# SignControlSchematic_v0.net
KiCad netlist of a schematic drawn in Altium Designer
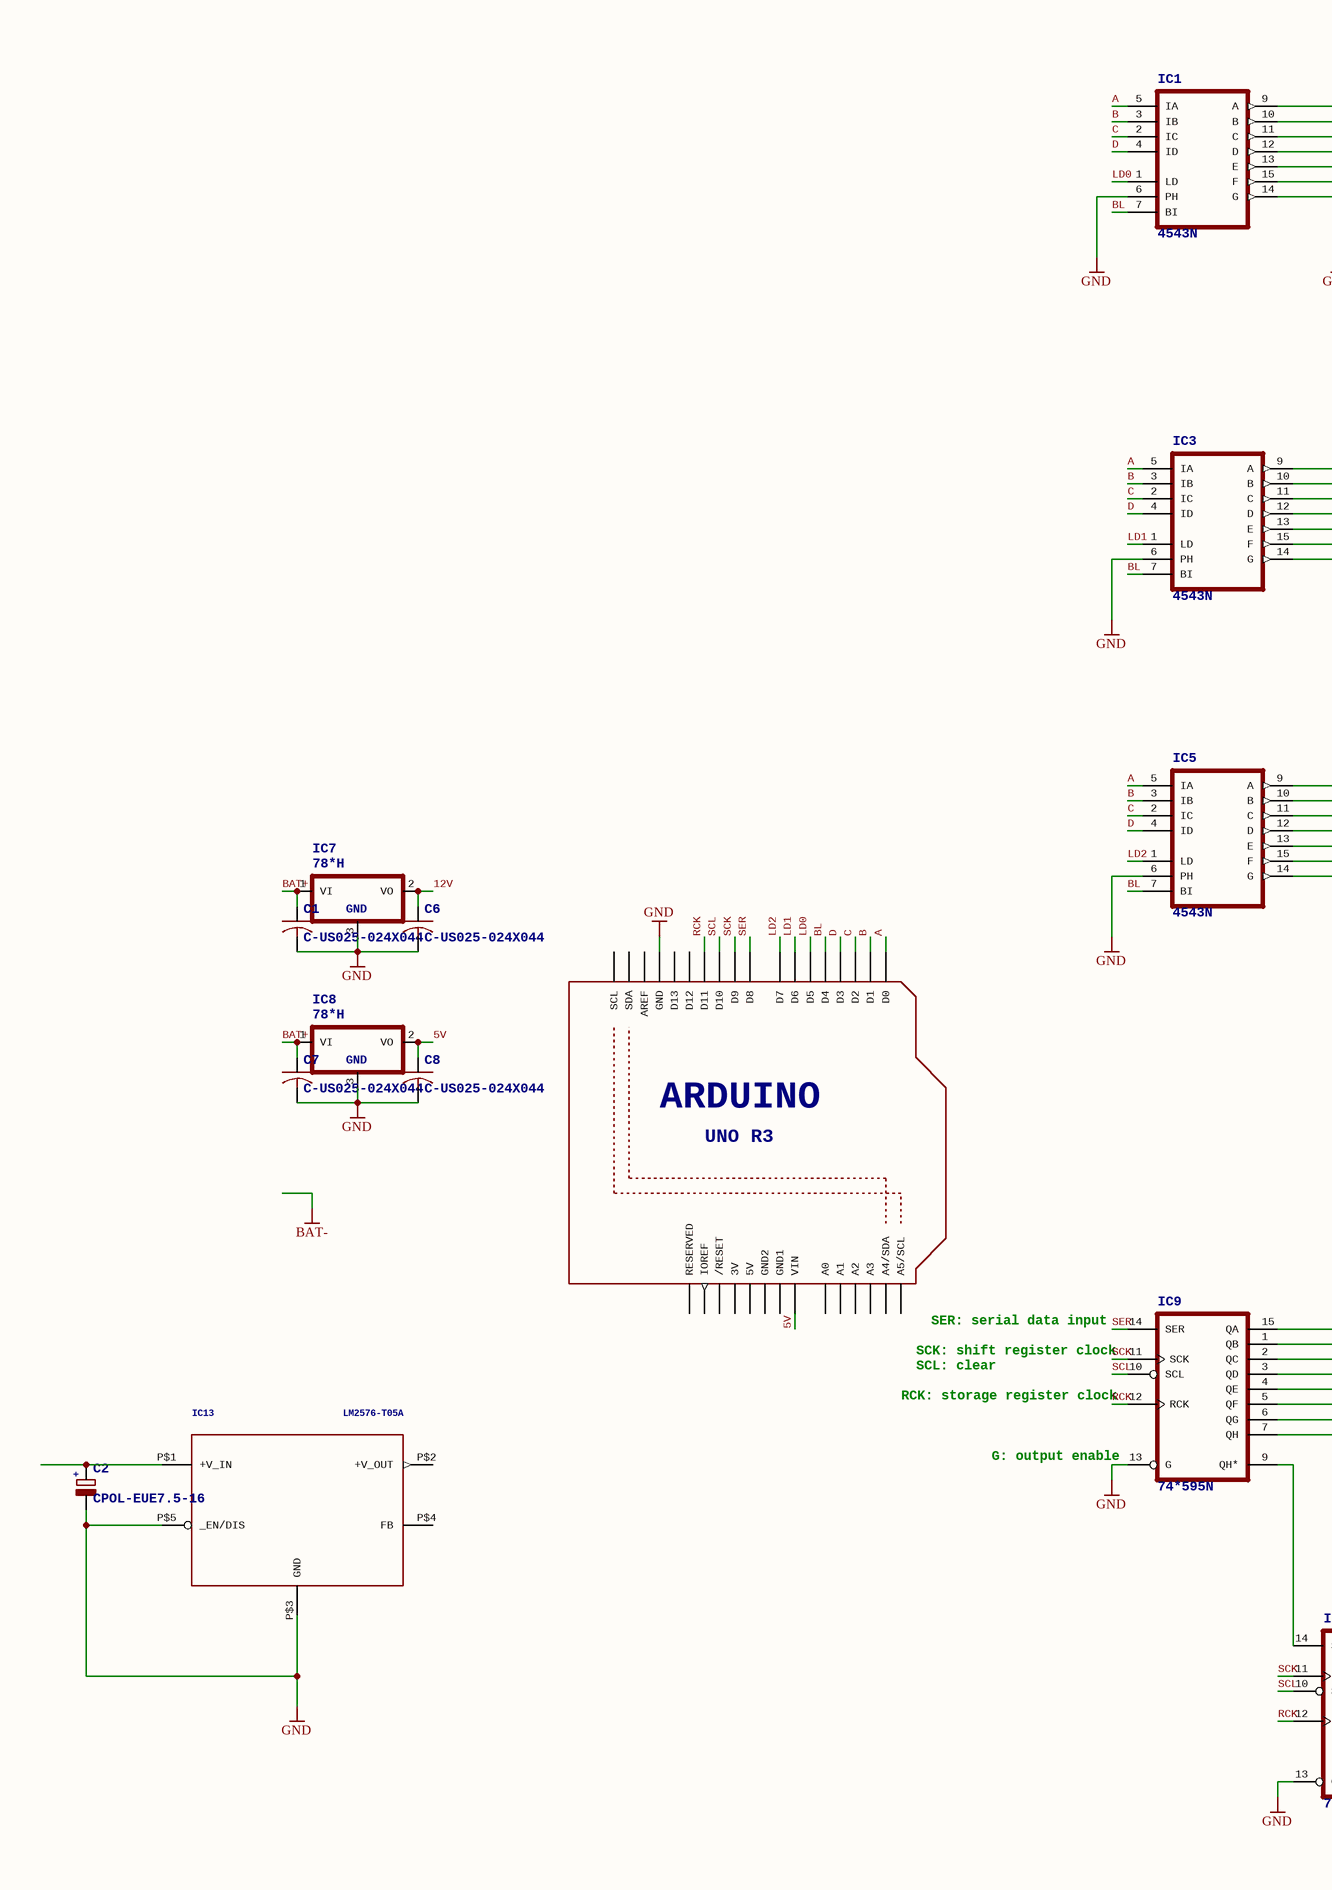
[diagram p0: SignControlSchematic_v0.SchDoc, left]
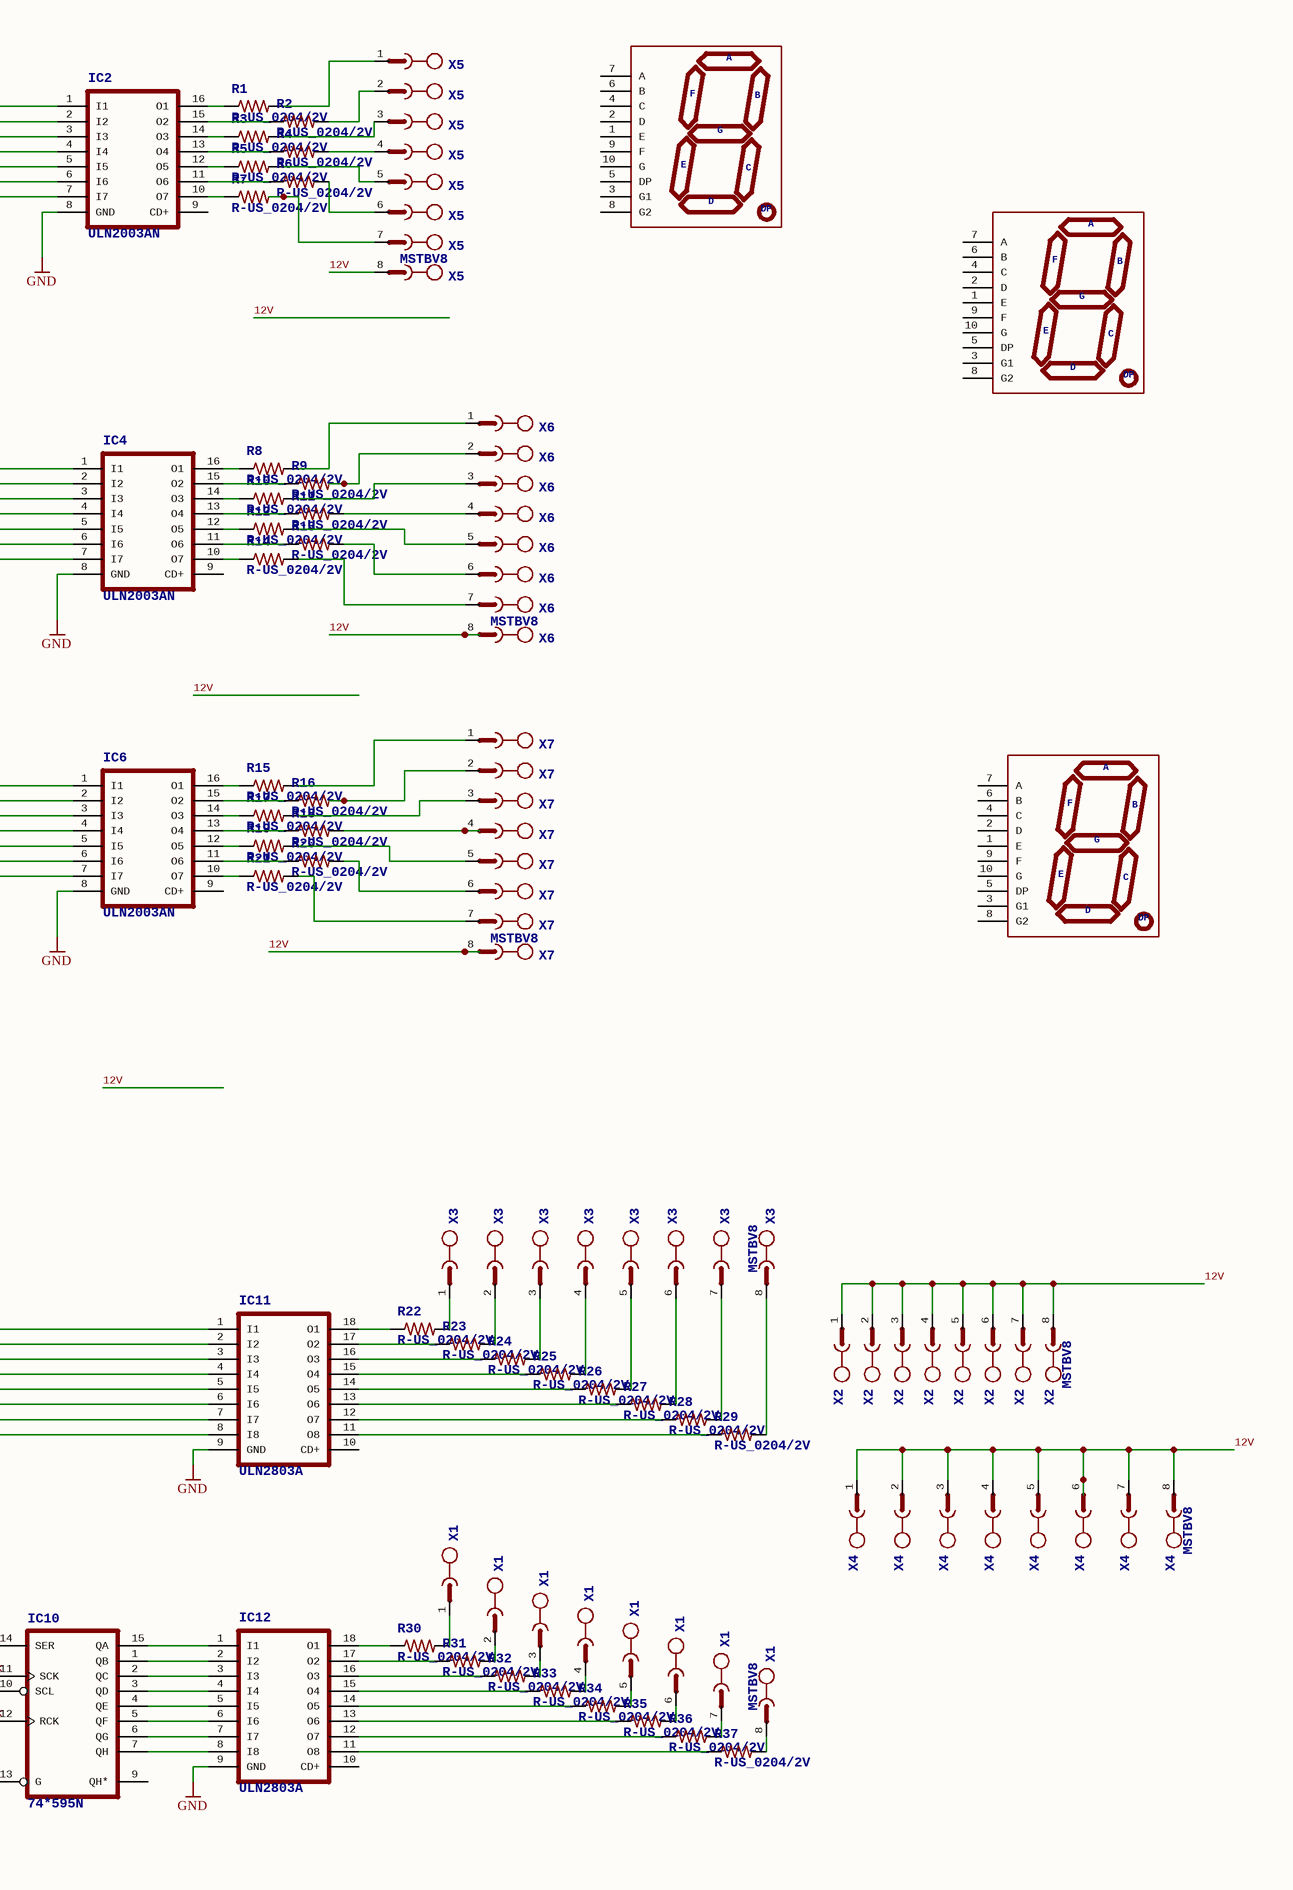
[diagram p1: SignControlSchematic_v0.SchDoc, right]

(export (version "E")
  (design (tool "Eeschema 10.0.6"))
  (components
    (comp (ref "C1")
      (value "C-US025-024X044")
      (footprint "C025-024X044")
      (description "<B>CAPACITOR</B>, American symbol")
      (fields (field (name ">NAME") "C1") (field (name ">VALUE") "C-US025-024X044"))
      (libsource (lib "adafruit") (part "C-US025-024X044"))
    )
    (comp (ref "C2")
      (value "CPOL-EUE7.5-16")
      (footprint "E7,5-16")
      (description "<B>POLARIZED CAPACITOR</B>, European symbol")
      (fields (field (name ">NAME") "C2") (field (name "+") "+") (field (name ">VALUE") "CPOL-EUE7.5-16"))
      (libsource (lib "resistor") (part "CPOL-EUE7.5-16"))
    )
    (comp (ref "C6")
      (value "C-US025-024X044")
      (footprint "C025-024X044")
      (description "<B>CAPACITOR</B>, American symbol")
      (fields (field (name ">NAME") "C6") (field (name ">VALUE") "C-US025-024X044"))
      (libsource (lib "adafruit") (part "C-US025-024X044"))
    )
    (comp (ref "C7")
      (value "C-US025-024X044")
      (footprint "C025-024X044")
      (description "<B>CAPACITOR</B>, American symbol")
      (fields (field (name ">NAME") "C7") (field (name ">VALUE") "C-US025-024X044"))
      (libsource (lib "adafruit") (part "C-US025-024X044"))
    )
    (comp (ref "C8")
      (value "C-US025-024X044")
      (footprint "C025-024X044")
      (description "<B>CAPACITOR</B>, American symbol")
      (fields (field (name ">NAME") "C8") (field (name ">VALUE") "C-US025-024X044"))
      (libsource (lib "adafruit") (part "C-US025-024X044"))
    )
    (comp (ref "IC1")
      (value "4543N")
      (footprint "DIL16")
      (description "BCD to 7-segment <b>LCD DECODER</b>")
      (fields (field (name ">NAME") "IC1") (field (name ">VALUE") "4543N"))
      (libsource (lib "45xx") (part "4543N"))
    )
    (comp (ref "IC2")
      (value "ULN2003AN")
      (footprint "DIL16")
      (description "<b>DRIVER ARRAY</b>")
      (fields (field (name ">NAME") "IC2") (field (name ">VALUE") "ULN2003AN"))
      (libsource (lib "uln-udn") (part "ULN2003AN"))
    )
    (comp (ref "IC3")
      (value "4543N")
      (footprint "DIL16")
      (description "BCD to 7-segment <b>LCD DECODER</b>")
      (fields (field (name ">NAME") "IC3") (field (name ">VALUE") "4543N"))
      (libsource (lib "45xx") (part "4543N"))
    )
    (comp (ref "IC4")
      (value "ULN2003AN")
      (footprint "DIL16")
      (description "<b>DRIVER ARRAY</b>")
      (fields (field (name ">NAME") "IC4") (field (name ">VALUE") "ULN2003AN"))
      (libsource (lib "uln-udn") (part "ULN2003AN"))
    )
    (comp (ref "IC5")
      (value "4543N")
      (footprint "DIL16")
      (description "BCD to 7-segment <b>LCD DECODER</b>")
      (fields (field (name ">NAME") "IC5") (field (name ">VALUE") "4543N"))
      (libsource (lib "45xx") (part "4543N"))
    )
    (comp (ref "IC6")
      (value "ULN2003AN")
      (footprint "DIL16")
      (description "<b>DRIVER ARRAY</b>")
      (fields (field (name ">NAME") "IC6") (field (name ">VALUE") "ULN2003AN"))
      (libsource (lib "uln-udn") (part "ULN2003AN"))
    )
    (comp (ref "IC7")
      (value "78*H")
      (footprint "TO39")
      (description "Positive <b>VOLTAGE REGULATOR</b>\n<p>\nAdded bigger pads to the TO-92 package")
      (fields (field (name ">NAME") "IC7") (field (name ">VALUE") "78*H") (field (name "GND") "GND"))
      (libsource (lib "adafruit") (part "78*H"))
    )
    (comp (ref "IC8")
      (value "78*H")
      (footprint "TO39")
      (description "Positive <b>VOLTAGE REGULATOR</b>\n<p>\nAdded bigger pads to the TO-92 package")
      (fields (field (name ">NAME") "IC8") (field (name ">VALUE") "78*H") (field (name "GND") "GND"))
      (libsource (lib "adafruit") (part "78*H"))
    )
    (comp (ref "IC9")
      (value "74*595N")
      (footprint "DIL16")
      (description "8-bit <b>SHIFT REGISTER</b>, output latch")
      (fields (field (name ">NAME") "IC9") (field (name ">VALUE") "74*595N"))
      (libsource (lib "74xx-eu") (part "74*595N"))
    )
    (comp (ref "IC10")
      (value "74*595N")
      (footprint "DIL16")
      (description "8-bit <b>SHIFT REGISTER</b>, output latch")
      (fields (field (name ">NAME") "IC10") (field (name ">VALUE") "74*595N"))
      (libsource (lib "74xx-eu") (part "74*595N"))
    )
    (comp (ref "IC11")
      (value "ULN2803A")
      (footprint "DIL18")
      (description "<b>DRIVER ARRAY</b>")
      (fields (field (name ">NAME") "IC11") (field (name ">VALUE") "ULN2803A"))
      (libsource (lib "uln-udn") (part "ULN2803A"))
    )
    (comp (ref "IC12")
      (value "ULN2803A")
      (footprint "DIL18")
      (description "<b>DRIVER ARRAY</b>")
      (fields (field (name ">NAME") "IC12") (field (name ">VALUE") "ULN2803A"))
      (libsource (lib "uln-udn") (part "ULN2803A"))
    )
    (comp (ref "IC13")
      (value "LM2576-T05A")
      (footprint "TO-220-5_IN-LINE")
      (description "LM2576/LM2576HV Series\nSIMPLE SWITCHER® 3A Step-Down Voltage Regulator\nIN-LINE PACKAGE")
      (fields (field (name ">NAME") "IC13") (field (name ">VALUE") "LM2576-T05A"))
      (libsource (lib "to220-custom") (part "LM2576-T05A"))
    )
    (comp (ref "R1")
      (value "R-US_0204/2V")
      (footprint "0204V")
      (description "<B>RESISTOR</B>, American symbol")
      (fields (field (name ">NAME") "R1") (field (name ">VALUE") "R-US_0204/2V"))
      (libsource (lib "adafruit") (part "R-US_0204/2V"))
    )
    (comp (ref "R2")
      (value "R-US_0204/2V")
      (footprint "0204V")
      (description "<B>RESISTOR</B>, American symbol")
      (fields (field (name ">NAME") "R2") (field (name ">VALUE") "R-US_0204/2V"))
      (libsource (lib "adafruit") (part "R-US_0204/2V"))
    )
    (comp (ref "R3")
      (value "R-US_0204/2V")
      (footprint "0204V")
      (description "<B>RESISTOR</B>, American symbol")
      (fields (field (name ">NAME") "R3") (field (name ">VALUE") "R-US_0204/2V"))
      (libsource (lib "adafruit") (part "R-US_0204/2V"))
    )
    (comp (ref "R4")
      (value "R-US_0204/2V")
      (footprint "0204V")
      (description "<B>RESISTOR</B>, American symbol")
      (fields (field (name ">NAME") "R4") (field (name ">VALUE") "R-US_0204/2V"))
      (libsource (lib "adafruit") (part "R-US_0204/2V"))
    )
    (comp (ref "R5")
      (value "R-US_0204/2V")
      (footprint "0204V")
      (description "<B>RESISTOR</B>, American symbol")
      (fields (field (name ">NAME") "R5") (field (name ">VALUE") "R-US_0204/2V"))
      (libsource (lib "adafruit") (part "R-US_0204/2V"))
    )
    (comp (ref "R6")
      (value "R-US_0204/2V")
      (footprint "0204V")
      (description "<B>RESISTOR</B>, American symbol")
      (fields (field (name ">NAME") "R6") (field (name ">VALUE") "R-US_0204/2V"))
      (libsource (lib "adafruit") (part "R-US_0204/2V"))
    )
    (comp (ref "R7")
      (value "R-US_0204/2V")
      (footprint "0204V")
      (description "<B>RESISTOR</B>, American symbol")
      (fields (field (name ">NAME") "R7") (field (name ">VALUE") "R-US_0204/2V"))
      (libsource (lib "adafruit") (part "R-US_0204/2V"))
    )
    (comp (ref "R8")
      (value "R-US_0204/2V")
      (footprint "0204V")
      (description "<B>RESISTOR</B>, American symbol")
      (fields (field (name ">NAME") "R8") (field (name ">VALUE") "R-US_0204/2V"))
      (libsource (lib "adafruit") (part "R-US_0204/2V"))
    )
    (comp (ref "R9")
      (value "R-US_0204/2V")
      (footprint "0204V")
      (description "<B>RESISTOR</B>, American symbol")
      (fields (field (name ">NAME") "R9") (field (name ">VALUE") "R-US_0204/2V"))
      (libsource (lib "adafruit") (part "R-US_0204/2V"))
    )
    (comp (ref "R10")
      (value "R-US_0204/2V")
      (footprint "0204V")
      (description "<B>RESISTOR</B>, American symbol")
      (fields (field (name ">NAME") "R10") (field (name ">VALUE") "R-US_0204/2V"))
      (libsource (lib "adafruit") (part "R-US_0204/2V"))
    )
    (comp (ref "R11")
      (value "R-US_0204/2V")
      (footprint "0204V")
      (description "<B>RESISTOR</B>, American symbol")
      (fields (field (name ">NAME") "R11") (field (name ">VALUE") "R-US_0204/2V"))
      (libsource (lib "adafruit") (part "R-US_0204/2V"))
    )
    (comp (ref "R12")
      (value "R-US_0204/2V")
      (footprint "0204V")
      (description "<B>RESISTOR</B>, American symbol")
      (fields (field (name ">NAME") "R12") (field (name ">VALUE") "R-US_0204/2V"))
      (libsource (lib "adafruit") (part "R-US_0204/2V"))
    )
    (comp (ref "R13")
      (value "R-US_0204/2V")
      (footprint "0204V")
      (description "<B>RESISTOR</B>, American symbol")
      (fields (field (name ">NAME") "R13") (field (name ">VALUE") "R-US_0204/2V"))
      (libsource (lib "adafruit") (part "R-US_0204/2V"))
    )
    (comp (ref "R14")
      (value "R-US_0204/2V")
      (footprint "0204V")
      (description "<B>RESISTOR</B>, American symbol")
      (fields (field (name ">NAME") "R14") (field (name ">VALUE") "R-US_0204/2V"))
      (libsource (lib "adafruit") (part "R-US_0204/2V"))
    )
    (comp (ref "R15")
      (value "R-US_0204/2V")
      (footprint "0204V")
      (description "<B>RESISTOR</B>, American symbol")
      (fields (field (name ">NAME") "R15") (field (name ">VALUE") "R-US_0204/2V"))
      (libsource (lib "adafruit") (part "R-US_0204/2V"))
    )
    (comp (ref "R16")
      (value "R-US_0204/2V")
      (footprint "0204V")
      (description "<B>RESISTOR</B>, American symbol")
      (fields (field (name ">NAME") "R16") (field (name ">VALUE") "R-US_0204/2V"))
      (libsource (lib "adafruit") (part "R-US_0204/2V"))
    )
    (comp (ref "R17")
      (value "R-US_0204/2V")
      (footprint "0204V")
      (description "<B>RESISTOR</B>, American symbol")
      (fields (field (name ">NAME") "R17") (field (name ">VALUE") "R-US_0204/2V"))
      (libsource (lib "adafruit") (part "R-US_0204/2V"))
    )
    (comp (ref "R18")
      (value "R-US_0204/2V")
      (footprint "0204V")
      (description "<B>RESISTOR</B>, American symbol")
      (fields (field (name ">NAME") "R18") (field (name ">VALUE") "R-US_0204/2V"))
      (libsource (lib "adafruit") (part "R-US_0204/2V"))
    )
    (comp (ref "R19")
      (value "R-US_0204/2V")
      (footprint "0204V")
      (description "<B>RESISTOR</B>, American symbol")
      (fields (field (name ">NAME") "R19") (field (name ">VALUE") "R-US_0204/2V"))
      (libsource (lib "adafruit") (part "R-US_0204/2V"))
    )
    (comp (ref "R20")
      (value "R-US_0204/2V")
      (footprint "0204V")
      (description "<B>RESISTOR</B>, American symbol")
      (fields (field (name ">NAME") "R20") (field (name ">VALUE") "R-US_0204/2V"))
      (libsource (lib "adafruit") (part "R-US_0204/2V"))
    )
    (comp (ref "R21")
      (value "R-US_0204/2V")
      (footprint "0204V")
      (description "<B>RESISTOR</B>, American symbol")
      (fields (field (name ">NAME") "R21") (field (name ">VALUE") "R-US_0204/2V"))
      (libsource (lib "adafruit") (part "R-US_0204/2V"))
    )
    (comp (ref "R22")
      (value "R-US_0204/2V")
      (footprint "0204V")
      (description "<B>RESISTOR</B>, American symbol")
      (fields (field (name ">NAME") "R22") (field (name ">VALUE") "R-US_0204/2V"))
      (libsource (lib "adafruit") (part "R-US_0204/2V"))
    )
    (comp (ref "R23")
      (value "R-US_0204/2V")
      (footprint "0204V")
      (description "<B>RESISTOR</B>, American symbol")
      (fields (field (name ">NAME") "R23") (field (name ">VALUE") "R-US_0204/2V"))
      (libsource (lib "adafruit") (part "R-US_0204/2V"))
    )
    (comp (ref "R24")
      (value "R-US_0204/2V")
      (footprint "0204V")
      (description "<B>RESISTOR</B>, American symbol")
      (fields (field (name ">NAME") "R24") (field (name ">VALUE") "R-US_0204/2V"))
      (libsource (lib "adafruit") (part "R-US_0204/2V"))
    )
    (comp (ref "R25")
      (value "R-US_0204/2V")
      (footprint "0204V")
      (description "<B>RESISTOR</B>, American symbol")
      (fields (field (name ">NAME") "R25") (field (name ">VALUE") "R-US_0204/2V"))
      (libsource (lib "adafruit") (part "R-US_0204/2V"))
    )
    (comp (ref "R26")
      (value "R-US_0204/2V")
      (footprint "0204V")
      (description "<B>RESISTOR</B>, American symbol")
      (fields (field (name ">NAME") "R26") (field (name ">VALUE") "R-US_0204/2V"))
      (libsource (lib "adafruit") (part "R-US_0204/2V"))
    )
    (comp (ref "R27")
      (value "R-US_0204/2V")
      (footprint "0204V")
      (description "<B>RESISTOR</B>, American symbol")
      (fields (field (name ">NAME") "R27") (field (name ">VALUE") "R-US_0204/2V"))
      (libsource (lib "adafruit") (part "R-US_0204/2V"))
    )
    (comp (ref "R28")
      (value "R-US_0204/2V")
      (footprint "0204V")
      (description "<B>RESISTOR</B>, American symbol")
      (fields (field (name ">NAME") "R28") (field (name ">VALUE") "R-US_0204/2V"))
      (libsource (lib "adafruit") (part "R-US_0204/2V"))
    )
    (comp (ref "R29")
      (value "R-US_0204/2V")
      (footprint "0204V")
      (description "<B>RESISTOR</B>, American symbol")
      (fields (field (name ">NAME") "R29") (field (name ">VALUE") "R-US_0204/2V"))
      (libsource (lib "adafruit") (part "R-US_0204/2V"))
    )
    (comp (ref "R30")
      (value "R-US_0204/2V")
      (footprint "0204V")
      (description "<B>RESISTOR</B>, American symbol")
      (fields (field (name ">NAME") "R30") (field (name ">VALUE") "R-US_0204/2V"))
      (libsource (lib "adafruit") (part "R-US_0204/2V"))
    )
    (comp (ref "R31")
      (value "R-US_0204/2V")
      (footprint "0204V")
      (description "<B>RESISTOR</B>, American symbol")
      (fields (field (name ">NAME") "R31") (field (name ">VALUE") "R-US_0204/2V"))
      (libsource (lib "adafruit") (part "R-US_0204/2V"))
    )
    (comp (ref "R32")
      (value "R-US_0204/2V")
      (footprint "0204V")
      (description "<B>RESISTOR</B>, American symbol")
      (fields (field (name ">NAME") "R32") (field (name ">VALUE") "R-US_0204/2V"))
      (libsource (lib "adafruit") (part "R-US_0204/2V"))
    )
    (comp (ref "R33")
      (value "R-US_0204/2V")
      (footprint "0204V")
      (description "<B>RESISTOR</B>, American symbol")
      (fields (field (name ">NAME") "R33") (field (name ">VALUE") "R-US_0204/2V"))
      (libsource (lib "adafruit") (part "R-US_0204/2V"))
    )
    (comp (ref "R34")
      (value "R-US_0204/2V")
      (footprint "0204V")
      (description "<B>RESISTOR</B>, American symbol")
      (fields (field (name ">NAME") "R34") (field (name ">VALUE") "R-US_0204/2V"))
      (libsource (lib "adafruit") (part "R-US_0204/2V"))
    )
    (comp (ref "R35")
      (value "R-US_0204/2V")
      (footprint "0204V")
      (description "<B>RESISTOR</B>, American symbol")
      (fields (field (name ">NAME") "R35") (field (name ">VALUE") "R-US_0204/2V"))
      (libsource (lib "adafruit") (part "R-US_0204/2V"))
    )
    (comp (ref "R36")
      (value "R-US_0204/2V")
      (footprint "0204V")
      (description "<B>RESISTOR</B>, American symbol")
      (fields (field (name ">NAME") "R36") (field (name ">VALUE") "R-US_0204/2V"))
      (libsource (lib "adafruit") (part "R-US_0204/2V"))
    )
    (comp (ref "R37")
      (value "R-US_0204/2V")
      (footprint "0204V")
      (description "<B>RESISTOR</B>, American symbol")
      (fields (field (name ">NAME") "R37") (field (name ">VALUE") "R-US_0204/2V"))
      (libsource (lib "adafruit") (part "R-US_0204/2V"))
    )
    (comp (ref "U$1")
      (value "7-SEGMENT-DISPLAY-1\"-RED")
      (footprint "7-SEGMENT-1\"PTH")
      (fields
        (field (name "A") "A")
        (field (name "B") "B")
        (field (name "C") "C")
        (field (name "D") "D")
        (field (name "E") "E")
        (field (name "F") "F")
        (field (name "G") "G")
        (field (name "DP") "DP")
      )
      (libsource (lib "SparkFun-Displays") (part "7-SEGMENT-DISPLAY-1{dblquote}-RED"))
    )
    (comp (ref "U$2")
      (value "7-SEGMENT-DISPLAY-1\"-RED")
      (footprint "7-SEGMENT-1\"PTH")
      (fields
        (field (name "A") "A")
        (field (name "B") "B")
        (field (name "C") "C")
        (field (name "D") "D")
        (field (name "E") "E")
        (field (name "F") "F")
        (field (name "G") "G")
        (field (name "DP") "DP")
      )
      (libsource (lib "SparkFun-Displays") (part "7-SEGMENT-DISPLAY-1{dblquote}-RED"))
    )
    (comp (ref "U$3")
      (value "7-SEGMENT-DISPLAY-1\"-RED")
      (footprint "7-SEGMENT-1\"PTH")
      (fields
        (field (name "A") "A")
        (field (name "B") "B")
        (field (name "C") "C")
        (field (name "D") "D")
        (field (name "E") "E")
        (field (name "F") "F")
        (field (name "G") "G")
        (field (name "DP") "DP")
      )
      (libsource (lib "SparkFun-Displays") (part "7-SEGMENT-DISPLAY-1{dblquote}-RED"))
    )
    (comp (ref "U1")
      (value "ARDUINOR3-BPLACE")
      (footprint "ARDUINOR3-BPLACE")
      (fields (field (name "ARDUINO") "ARDUINO") (field (name "UNO R3") "UNO R3"))
      (libsource (lib "adafruit") (part "ARDUINOR3-BPLACE"))
    )
    (comp (ref "X1")
      (value "MSTBV8")
      (footprint "MSTBV8")
      (description "<b>PHOENIX</b>")
      (fields
        (field (name "MPN") "MSTBV 2,5/8-GF-5.08")
        (field (name ">NAME") "X1")
        (field (name ">VALUE") "MSTBV8")
      )
      (libsource (lib "") (part "MSTBV8_4"))
    )
    (comp (ref "X2")
      (value "MSTBV8")
      (footprint "MSTBV8")
      (description "<b>PHOENIX</b>")
      (fields
        (field (name "MPN") "MSTBV 2,5/8-GF-5.08")
        (field (name ">NAME") "X2")
        (field (name ">VALUE") "MSTBV8")
      )
      (libsource (lib "") (part "MSTBV8_4"))
    )
    (comp (ref "X3")
      (value "MSTBV8")
      (footprint "MSTBV8")
      (description "<b>PHOENIX</b>")
      (fields
        (field (name "MPN") "MSTBV 2,5/8-GF-5.08")
        (field (name ">NAME") "X3")
        (field (name ">VALUE") "MSTBV8")
      )
      (libsource (lib "") (part "MSTBV8_1"))
    )
    (comp (ref "X4")
      (value "MSTBV8")
      (footprint "MSTBV8")
      (description "<b>PHOENIX</b>")
      (fields
        (field (name "MPN") "MSTBV 2,5/8-GF-5.08")
        (field (name ">NAME") "X4")
        (field (name ">VALUE") "MSTBV8")
      )
      (libsource (lib "") (part "MSTBV8_7"))
    )
    (comp (ref "X5")
      (value "MSTBV8")
      (footprint "MSTBV8")
      (description "<b>PHOENIX</b>")
      (fields
        (field (name "MPN") "MSTBV 2,5/8-GF-5.08")
        (field (name ">VALUE") "MSTBV8")
        (field (name ">NAME") "X5")
      )
      (libsource (lib "") (part "MSTBV8_7"))
    )
    (comp (ref "X6")
      (value "MSTBV8")
      (footprint "MSTBV8")
      (description "<b>PHOENIX</b>")
      (fields
        (field (name "MPN") "MSTBV 2,5/8-GF-5.08")
        (field (name ">VALUE") "MSTBV8")
        (field (name ">NAME") "X6")
      )
      (libsource (lib "con-phoenix-508") (part "MSTBV8"))
    )
    (comp (ref "X7")
      (value "MSTBV8")
      (footprint "MSTBV8")
      (description "<b>PHOENIX</b>")
      (fields
        (field (name "MPN") "MSTBV 2,5/8-GF-5.08")
        (field (name ">NAME") "X7")
        (field (name ">VALUE") "MSTBV8")
      )
      (libsource (lib "") (part "MSTBV8_4"))
    )
  )
  (nets
    (net (code "1") (name "/5V") (class "Default")
      (node (ref "C8") (pin "1") (pinfunction "1_1") (pintype "passive"))
      (node (ref "IC8") (pin "2") (pinfunction "VO_2") (pintype "passive"))
      (node (ref "U1") (pin "VIN") (pinfunction "VIN_VIN") (pintype "power_in"))
    )
    (net (code "2") (name "/12V") (class "Default")
      (node (ref "C6") (pin "1") (pinfunction "1_1") (pintype "passive"))
      (node (ref "IC7") (pin "2") (pinfunction "VO_2") (pintype "passive"))
      (node (ref "X2") (pin "1") (pinfunction "1_1") (pintype "passive"))
      (node (ref "X2") (pin "2") (pinfunction "1_2") (pintype "passive"))
      (node (ref "X2") (pin "3") (pinfunction "1_3") (pintype "passive"))
      (node (ref "X2") (pin "4") (pinfunction "1_4") (pintype "passive"))
      (node (ref "X2") (pin "5") (pinfunction "1_5") (pintype "passive"))
      (node (ref "X2") (pin "6") (pinfunction "1_6") (pintype "passive"))
      (node (ref "X2") (pin "7") (pinfunction "1_7") (pintype "passive"))
      (node (ref "X2") (pin "8") (pinfunction "1_8") (pintype "passive"))
      (node (ref "X4") (pin "1") (pinfunction "1_1") (pintype "passive"))
      (node (ref "X4") (pin "2") (pinfunction "1_2") (pintype "passive"))
      (node (ref "X4") (pin "3") (pinfunction "1_3") (pintype "passive"))
      (node (ref "X4") (pin "4") (pinfunction "1_4") (pintype "passive"))
      (node (ref "X4") (pin "5") (pinfunction "1_5") (pintype "passive"))
      (node (ref "X4") (pin "6") (pinfunction "1_6") (pintype "passive"))
      (node (ref "X4") (pin "7") (pinfunction "1_7") (pintype "passive"))
      (node (ref "X4") (pin "8") (pinfunction "1_8") (pintype "passive"))
      (node (ref "X5") (pin "8") (pinfunction "1_8") (pintype "passive"))
      (node (ref "X6") (pin "8") (pinfunction "1_8") (pintype "passive"))
      (node (ref "X7") (pin "8") (pinfunction "1_8") (pintype "passive"))
    )
    (net (code "3") (name "/A") (class "Default")
      (node (ref "IC1") (pin "5") (pinfunction "IA_5") (pintype "passive"))
      (node (ref "IC3") (pin "5") (pinfunction "IA_5") (pintype "passive"))
      (node (ref "IC5") (pin "5") (pinfunction "IA_5") (pintype "passive"))
      (node (ref "U1") (pin "D0") (pinfunction "D0_D0") (pintype "passive"))
    )
    (net (code "4") (name "/B") (class "Default")
      (node (ref "IC1") (pin "3") (pinfunction "IB_3") (pintype "passive"))
      (node (ref "IC3") (pin "3") (pinfunction "IB_3") (pintype "passive"))
      (node (ref "IC5") (pin "3") (pinfunction "IB_3") (pintype "passive"))
      (node (ref "U1") (pin "D1") (pinfunction "D1_D1") (pintype "passive"))
    )
    (net (code "5") (name "/BAT+") (class "Default")
      (node (ref "C1") (pin "1") (pinfunction "1_1") (pintype "passive"))
      (node (ref "C7") (pin "1") (pinfunction "1_1") (pintype "passive"))
      (node (ref "IC7") (pin "1") (pinfunction "VI_1") (pintype "passive"))
      (node (ref "IC8") (pin "1") (pinfunction "VI_1") (pintype "passive"))
    )
    (net (code "6") (name "/BL") (class "Default")
      (node (ref "IC1") (pin "7") (pinfunction "BI_7") (pintype "passive"))
      (node (ref "IC3") (pin "7") (pinfunction "BI_7") (pintype "passive"))
      (node (ref "IC5") (pin "7") (pinfunction "BI_7") (pintype "passive"))
      (node (ref "U1") (pin "D4") (pinfunction "D4_D4") (pintype "passive"))
    )
    (net (code "7") (name "/C") (class "Default")
      (node (ref "IC1") (pin "2") (pinfunction "IC_2") (pintype "passive"))
      (node (ref "IC3") (pin "2") (pinfunction "IC_2") (pintype "passive"))
      (node (ref "IC5") (pin "2") (pinfunction "IC_2") (pintype "passive"))
      (node (ref "U1") (pin "D2") (pinfunction "D2_D2") (pintype "passive"))
    )
    (net (code "8") (name "/D") (class "Default")
      (node (ref "IC1") (pin "4") (pinfunction "ID_4") (pintype "passive"))
      (node (ref "IC3") (pin "4") (pinfunction "ID_4") (pintype "passive"))
      (node (ref "IC5") (pin "4") (pinfunction "ID_4") (pintype "passive"))
      (node (ref "U1") (pin "D3") (pinfunction "D3_D3") (pintype "passive"))
    )
    (net (code "9") (name "/LD0") (class "Default")
      (node (ref "IC1") (pin "1") (pinfunction "LD_1") (pintype "passive"))
      (node (ref "U1") (pin "D5") (pinfunction "D5_D5") (pintype "passive"))
    )
    (net (code "10") (name "/LD1") (class "Default")
      (node (ref "IC3") (pin "1") (pinfunction "LD_1") (pintype "passive"))
      (node (ref "U1") (pin "D6") (pinfunction "D6_D6") (pintype "passive"))
    )
    (net (code "11") (name "/LD2") (class "Default")
      (node (ref "IC5") (pin "1") (pinfunction "LD_1") (pintype "passive"))
      (node (ref "U1") (pin "D7") (pinfunction "D7_D7") (pintype "passive"))
    )
    (net (code "12") (name "/RCK") (class "Default")
      (node (ref "IC10") (pin "12") (pinfunction "RCK_12") (pintype "passive"))
      (node (ref "IC9") (pin "12") (pinfunction "RCK_12") (pintype "passive"))
      (node (ref "U1") (pin "D11") (pinfunction "D11_D11") (pintype "passive"))
    )
    (net (code "13") (name "/SCK") (class "Default")
      (node (ref "IC10") (pin "11") (pinfunction "SCK_11") (pintype "passive"))
      (node (ref "IC9") (pin "11") (pinfunction "SCK_11") (pintype "passive"))
      (node (ref "U1") (pin "D9") (pinfunction "D9_D9") (pintype "passive"))
    )
    (net (code "14") (name "/SCL") (class "Default")
      (node (ref "IC10") (pin "10") (pinfunction "SCL_10") (pintype "passive"))
      (node (ref "IC9") (pin "10") (pinfunction "SCL_10") (pintype "passive"))
      (node (ref "U1") (pin "D10") (pinfunction "D10_D10") (pintype "passive"))
    )
    (net (code "15") (name "/SER") (class "Default")
      (node (ref "IC9") (pin "14") (pinfunction "SER_14") (pintype "passive"))
      (node (ref "U1") (pin "D8") (pinfunction "D8_D8") (pintype "passive"))
    )
    (net (code "17") (name "GND") (class "Default")
      (node (ref "C1") (pin "2") (pinfunction "2_2") (pintype "passive"))
      (node (ref "C2") (pin "-") (pinfunction "-_-") (pintype "passive"))
      (node (ref "C6") (pin "2") (pinfunction "2_2") (pintype "passive"))
      (node (ref "C7") (pin "2") (pinfunction "2_2") (pintype "passive"))
      (node (ref "C8") (pin "2") (pinfunction "2_2") (pintype "passive"))
      (node (ref "IC1") (pin "6") (pinfunction "PH_6") (pintype "passive"))
      (node (ref "IC10") (pin "13") (pinfunction "G_13") (pintype "passive"))
      (node (ref "IC11") (pin "9") (pinfunction "GND_9") (pintype "power_in"))
      (node (ref "IC12") (pin "9") (pinfunction "GND_9") (pintype "power_in"))
      (node (ref "IC13") (pin "P$3") (pinfunction "GND_P$3") (pintype "power_in"))
      (node (ref "IC13") (pin "P$5") (pinfunction "_EN/DIS_P$5") (pintype "passive"))
      (node (ref "IC2") (pin "8") (pinfunction "GND_8") (pintype "power_in"))
      (node (ref "IC3") (pin "6") (pinfunction "PH_6") (pintype "passive"))
      (node (ref "IC4") (pin "8") (pinfunction "GND_8") (pintype "power_in"))
      (node (ref "IC5") (pin "6") (pinfunction "PH_6") (pintype "passive"))
      (node (ref "IC6") (pin "8") (pinfunction "GND_8") (pintype "power_in"))
      (node (ref "IC7") (pin "3") (pinfunction "GND_3") (pintype "passive"))
      (node (ref "IC8") (pin "3") (pinfunction "GND_3") (pintype "passive"))
      (node (ref "IC9") (pin "13") (pinfunction "G_13") (pintype "passive"))
      (node (ref "U1") (pin "GND") (pinfunction "GND_GND") (pintype "power_in"))
    )
    (net (code "18") (name "Net-(IC1-A)") (class "Default")
      (node (ref "IC1") (pin "9") (pinfunction "A_9") (pintype "output"))
      (node (ref "IC2") (pin "1") (pinfunction "I1_1") (pintype "passive"))
    )
    (net (code "19") (name "Net-(IC1-B)") (class "Default")
      (node (ref "IC1") (pin "10") (pinfunction "B_10") (pintype "output"))
      (node (ref "IC2") (pin "2") (pinfunction "I2_2") (pintype "passive"))
    )
    (net (code "20") (name "Net-(IC1-C)") (class "Default")
      (node (ref "IC1") (pin "11") (pinfunction "C_11") (pintype "output"))
      (node (ref "IC2") (pin "3") (pinfunction "I3_3") (pintype "passive"))
    )
    (net (code "21") (name "Net-(IC1-D)") (class "Default")
      (node (ref "IC1") (pin "12") (pinfunction "D_12") (pintype "output"))
      (node (ref "IC2") (pin "4") (pinfunction "I4_4") (pintype "passive"))
    )
    (net (code "22") (name "Net-(IC1-E)") (class "Default")
      (node (ref "IC1") (pin "13") (pinfunction "E_13") (pintype "output"))
      (node (ref "IC2") (pin "5") (pinfunction "I5_5") (pintype "passive"))
    )
    (net (code "23") (name "Net-(IC1-F)") (class "Default")
      (node (ref "IC1") (pin "15") (pinfunction "F_15") (pintype "output"))
      (node (ref "IC2") (pin "6") (pinfunction "I6_6") (pintype "passive"))
    )
    (net (code "24") (name "Net-(IC1-G)") (class "Default")
      (node (ref "IC1") (pin "14") (pinfunction "G_14") (pintype "output"))
      (node (ref "IC2") (pin "7") (pinfunction "I7_7") (pintype "passive"))
    )
    (net (code "25") (name "Net-(IC2-O1)") (class "Default")
      (node (ref "IC2") (pin "16") (pinfunction "O1_16") (pintype "open_collector"))
      (node (ref "R1") (pin "1") (pinfunction "1_1") (pintype "passive"))
    )
    (net (code "26") (name "Net-(IC2-O2)") (class "Default")
      (node (ref "IC2") (pin "15") (pinfunction "O2_15") (pintype "open_collector"))
      (node (ref "R2") (pin "1") (pinfunction "1_1") (pintype "passive"))
    )
    (net (code "27") (name "Net-(IC2-O3)") (class "Default")
      (node (ref "IC2") (pin "14") (pinfunction "O3_14") (pintype "open_collector"))
      (node (ref "R3") (pin "1") (pinfunction "1_1") (pintype "passive"))
    )
    (net (code "28") (name "Net-(IC2-O4)") (class "Default")
      (node (ref "IC2") (pin "13") (pinfunction "O4_13") (pintype "open_collector"))
      (node (ref "R4") (pin "1") (pinfunction "1_1") (pintype "passive"))
    )
    (net (code "29") (name "Net-(IC2-O5)") (class "Default")
      (node (ref "IC2") (pin "12") (pinfunction "O5_12") (pintype "open_collector"))
      (node (ref "R5") (pin "1") (pinfunction "1_1") (pintype "passive"))
    )
    (net (code "30") (name "Net-(IC2-O6)") (class "Default")
      (node (ref "IC2") (pin "11") (pinfunction "O6_11") (pintype "open_collector"))
      (node (ref "R6") (pin "1") (pinfunction "1_1") (pintype "passive"))
    )
    (net (code "31") (name "Net-(IC2-O7)") (class "Default")
      (node (ref "IC2") (pin "10") (pinfunction "O7_10") (pintype "open_collector"))
      (node (ref "R7") (pin "1") (pinfunction "1_1") (pintype "passive"))
    )
    (net (code "32") (name "Net-(IC3-A)") (class "Default")
      (node (ref "IC3") (pin "9") (pinfunction "A_9") (pintype "output"))
      (node (ref "IC4") (pin "1") (pinfunction "I1_1") (pintype "passive"))
    )
    (net (code "33") (name "Net-(IC3-B)") (class "Default")
      (node (ref "IC3") (pin "10") (pinfunction "B_10") (pintype "output"))
      (node (ref "IC4") (pin "2") (pinfunction "I2_2") (pintype "passive"))
    )
    (net (code "34") (name "Net-(IC3-C)") (class "Default")
      (node (ref "IC3") (pin "11") (pinfunction "C_11") (pintype "output"))
      (node (ref "IC4") (pin "3") (pinfunction "I3_3") (pintype "passive"))
    )
    (net (code "35") (name "Net-(IC3-D)") (class "Default")
      (node (ref "IC3") (pin "12") (pinfunction "D_12") (pintype "output"))
      (node (ref "IC4") (pin "4") (pinfunction "I4_4") (pintype "passive"))
    )
    (net (code "36") (name "Net-(IC3-E)") (class "Default")
      (node (ref "IC3") (pin "13") (pinfunction "E_13") (pintype "output"))
      (node (ref "IC4") (pin "5") (pinfunction "I5_5") (pintype "passive"))
    )
    (net (code "37") (name "Net-(IC3-F)") (class "Default")
      (node (ref "IC3") (pin "15") (pinfunction "F_15") (pintype "output"))
      (node (ref "IC4") (pin "6") (pinfunction "I6_6") (pintype "passive"))
    )
    (net (code "38") (name "Net-(IC3-G)") (class "Default")
      (node (ref "IC3") (pin "14") (pinfunction "G_14") (pintype "output"))
      (node (ref "IC4") (pin "7") (pinfunction "I7_7") (pintype "passive"))
    )
    (net (code "39") (name "Net-(IC4-O1)") (class "Default")
      (node (ref "IC4") (pin "16") (pinfunction "O1_16") (pintype "open_collector"))
      (node (ref "R8") (pin "1") (pinfunction "1_1") (pintype "passive"))
    )
    (net (code "40") (name "Net-(IC4-O2)") (class "Default")
      (node (ref "IC4") (pin "15") (pinfunction "O2_15") (pintype "open_collector"))
      (node (ref "R9") (pin "1") (pinfunction "1_1") (pintype "passive"))
    )
    (net (code "41") (name "Net-(IC4-O3)") (class "Default")
      (node (ref "IC4") (pin "14") (pinfunction "O3_14") (pintype "open_collector"))
      (node (ref "R10") (pin "1") (pinfunction "1_1") (pintype "passive"))
    )
    (net (code "42") (name "Net-(IC4-O4)") (class "Default")
      (node (ref "IC4") (pin "13") (pinfunction "O4_13") (pintype "open_collector"))
      (node (ref "R11") (pin "1") (pinfunction "1_1") (pintype "passive"))
    )
    (net (code "43") (name "Net-(IC4-O5)") (class "Default")
      (node (ref "IC4") (pin "12") (pinfunction "O5_12") (pintype "open_collector"))
      (node (ref "R12") (pin "1") (pinfunction "1_1") (pintype "passive"))
    )
    (net (code "44") (name "Net-(IC4-O6)") (class "Default")
      (node (ref "IC4") (pin "11") (pinfunction "O6_11") (pintype "open_collector"))
      (node (ref "R13") (pin "1") (pinfunction "1_1") (pintype "passive"))
    )
    (net (code "45") (name "Net-(IC4-O7)") (class "Default")
      (node (ref "IC4") (pin "10") (pinfunction "O7_10") (pintype "open_collector"))
      (node (ref "R14") (pin "1") (pinfunction "1_1") (pintype "passive"))
    )
    (net (code "46") (name "Net-(IC5-A)") (class "Default")
      (node (ref "IC5") (pin "9") (pinfunction "A_9") (pintype "output"))
      (node (ref "IC6") (pin "1") (pinfunction "I1_1") (pintype "passive"))
    )
    (net (code "47") (name "Net-(IC5-B)") (class "Default")
      (node (ref "IC5") (pin "10") (pinfunction "B_10") (pintype "output"))
      (node (ref "IC6") (pin "2") (pinfunction "I2_2") (pintype "passive"))
    )
    (net (code "48") (name "Net-(IC5-C)") (class "Default")
      (node (ref "IC5") (pin "11") (pinfunction "C_11") (pintype "output"))
      (node (ref "IC6") (pin "3") (pinfunction "I3_3") (pintype "passive"))
    )
    (net (code "49") (name "Net-(IC5-D)") (class "Default")
      (node (ref "IC5") (pin "12") (pinfunction "D_12") (pintype "output"))
      (node (ref "IC6") (pin "4") (pinfunction "I4_4") (pintype "passive"))
    )
    (net (code "50") (name "Net-(IC5-E)") (class "Default")
      (node (ref "IC5") (pin "13") (pinfunction "E_13") (pintype "output"))
      (node (ref "IC6") (pin "5") (pinfunction "I5_5") (pintype "passive"))
    )
    (net (code "51") (name "Net-(IC5-F)") (class "Default")
      (node (ref "IC5") (pin "15") (pinfunction "F_15") (pintype "output"))
      (node (ref "IC6") (pin "6") (pinfunction "I6_6") (pintype "passive"))
    )
    (net (code "52") (name "Net-(IC5-G)") (class "Default")
      (node (ref "IC5") (pin "14") (pinfunction "G_14") (pintype "output"))
      (node (ref "IC6") (pin "7") (pinfunction "I7_7") (pintype "passive"))
    )
    (net (code "53") (name "Net-(IC6-O1)") (class "Default")
      (node (ref "IC6") (pin "16") (pinfunction "O1_16") (pintype "open_collector"))
      (node (ref "R15") (pin "1") (pinfunction "1_1") (pintype "passive"))
    )
    (net (code "54") (name "Net-(IC6-O2)") (class "Default")
      (node (ref "IC6") (pin "15") (pinfunction "O2_15") (pintype "open_collector"))
      (node (ref "R16") (pin "1") (pinfunction "1_1") (pintype "passive"))
    )
    (net (code "55") (name "Net-(IC6-O3)") (class "Default")
      (node (ref "IC6") (pin "14") (pinfunction "O3_14") (pintype "open_collector"))
      (node (ref "R17") (pin "1") (pinfunction "1_1") (pintype "passive"))
    )
    (net (code "56") (name "Net-(IC6-O4)") (class "Default")
      (node (ref "IC6") (pin "13") (pinfunction "O4_13") (pintype "open_collector"))
      (node (ref "R18") (pin "1") (pinfunction "1_1") (pintype "passive"))
    )
    (net (code "57") (name "Net-(IC6-O5)") (class "Default")
      (node (ref "IC6") (pin "12") (pinfunction "O5_12") (pintype "open_collector"))
      (node (ref "R19") (pin "1") (pinfunction "1_1") (pintype "passive"))
    )
    (net (code "58") (name "Net-(IC6-O6)") (class "Default")
      (node (ref "IC6") (pin "11") (pinfunction "O6_11") (pintype "open_collector"))
      (node (ref "R20") (pin "1") (pinfunction "1_1") (pintype "passive"))
    )
    (net (code "59") (name "Net-(IC6-O7)") (class "Default")
      (node (ref "IC6") (pin "10") (pinfunction "O7_10") (pintype "open_collector"))
      (node (ref "R21") (pin "1") (pinfunction "1_1") (pintype "passive"))
    )
    (net (code "60") (name "Net-(IC10-QA)") (class "Default")
      (node (ref "IC10") (pin "15") (pinfunction "QA_15") (pintype "tri_state"))
      (node (ref "IC12") (pin "1") (pinfunction "I1_1") (pintype "passive"))
    )
    (net (code "61") (name "Net-(IC10-QB)") (class "Default")
      (node (ref "IC10") (pin "1") (pinfunction "QB_1") (pintype "tri_state"))
      (node (ref "IC12") (pin "2") (pinfunction "I2_2") (pintype "passive"))
    )
    (net (code "62") (name "Net-(IC10-QC)") (class "Default")
      (node (ref "IC10") (pin "2") (pinfunction "QC_2") (pintype "tri_state"))
      (node (ref "IC12") (pin "3") (pinfunction "I3_3") (pintype "passive"))
    )
    (net (code "63") (name "Net-(IC10-QD)") (class "Default")
      (node (ref "IC10") (pin "3") (pinfunction "QD_3") (pintype "tri_state"))
      (node (ref "IC12") (pin "4") (pinfunction "I4_4") (pintype "passive"))
    )
    (net (code "64") (name "Net-(IC10-QE)") (class "Default")
      (node (ref "IC10") (pin "4") (pinfunction "QE_4") (pintype "tri_state"))
      (node (ref "IC12") (pin "5") (pinfunction "I5_5") (pintype "passive"))
    )
    (net (code "65") (name "Net-(IC10-QF)") (class "Default")
      (node (ref "IC10") (pin "5") (pinfunction "QF_5") (pintype "tri_state"))
      (node (ref "IC12") (pin "6") (pinfunction "I6_6") (pintype "passive"))
    )
    (net (code "66") (name "Net-(IC10-QG)") (class "Default")
      (node (ref "IC10") (pin "6") (pinfunction "QG_6") (pintype "tri_state"))
      (node (ref "IC12") (pin "7") (pinfunction "I7_7") (pintype "passive"))
    )
    (net (code "67") (name "Net-(IC10-QH)") (class "Default")
      (node (ref "IC10") (pin "7") (pinfunction "QH_7") (pintype "tri_state"))
      (node (ref "IC12") (pin "8") (pinfunction "I8_8") (pintype "passive"))
    )
    (net (code "68") (name "Net-(IC10-SER)") (class "Default")
      (node (ref "IC10") (pin "14") (pinfunction "SER_14") (pintype "passive"))
      (node (ref "IC9") (pin "9") (pinfunction "QH*_9") (pintype "tri_state"))
    )
    (net (code "69") (name "Net-(IC11-I1)") (class "Default")
      (node (ref "IC11") (pin "1") (pinfunction "I1_1") (pintype "passive"))
      (node (ref "IC9") (pin "15") (pinfunction "QA_15") (pintype "tri_state"))
    )
    (net (code "70") (name "Net-(IC11-I2)") (class "Default")
      (node (ref "IC11") (pin "2") (pinfunction "I2_2") (pintype "passive"))
      (node (ref "IC9") (pin "1") (pinfunction "QB_1") (pintype "tri_state"))
    )
    (net (code "71") (name "Net-(IC11-I3)") (class "Default")
      (node (ref "IC11") (pin "3") (pinfunction "I3_3") (pintype "passive"))
      (node (ref "IC9") (pin "2") (pinfunction "QC_2") (pintype "tri_state"))
    )
    (net (code "72") (name "Net-(IC11-I4)") (class "Default")
      (node (ref "IC11") (pin "4") (pinfunction "I4_4") (pintype "passive"))
      (node (ref "IC9") (pin "3") (pinfunction "QD_3") (pintype "tri_state"))
    )
    (net (code "73") (name "Net-(IC11-I5)") (class "Default")
      (node (ref "IC11") (pin "5") (pinfunction "I5_5") (pintype "passive"))
      (node (ref "IC9") (pin "4") (pinfunction "QE_4") (pintype "tri_state"))
    )
    (net (code "74") (name "Net-(IC11-I6)") (class "Default")
      (node (ref "IC11") (pin "6") (pinfunction "I6_6") (pintype "passive"))
      (node (ref "IC9") (pin "5") (pinfunction "QF_5") (pintype "tri_state"))
    )
    (net (code "75") (name "Net-(IC11-I7)") (class "Default")
      (node (ref "IC11") (pin "7") (pinfunction "I7_7") (pintype "passive"))
      (node (ref "IC9") (pin "6") (pinfunction "QG_6") (pintype "tri_state"))
    )
    (net (code "76") (name "Net-(IC11-I8)") (class "Default")
      (node (ref "IC11") (pin "8") (pinfunction "I8_8") (pintype "passive"))
      (node (ref "IC9") (pin "7") (pinfunction "QH_7") (pintype "tri_state"))
    )
    (net (code "77") (name "Net-(IC11-O1)") (class "Default")
      (node (ref "IC11") (pin "18") (pinfunction "O1_18") (pintype "open_collector"))
      (node (ref "R22") (pin "1") (pinfunction "1_1") (pintype "passive"))
    )
    (net (code "78") (name "Net-(IC11-O2)") (class "Default")
      (node (ref "IC11") (pin "17") (pinfunction "O2_17") (pintype "open_collector"))
      (node (ref "R23") (pin "1") (pinfunction "1_1") (pintype "passive"))
    )
    (net (code "79") (name "Net-(IC11-O3)") (class "Default")
      (node (ref "IC11") (pin "16") (pinfunction "O3_16") (pintype "open_collector"))
      (node (ref "R24") (pin "1") (pinfunction "1_1") (pintype "passive"))
    )
    (net (code "80") (name "Net-(IC11-O4)") (class "Default")
      (node (ref "IC11") (pin "15") (pinfunction "O4_15") (pintype "open_collector"))
      (node (ref "R25") (pin "1") (pinfunction "1_1") (pintype "passive"))
    )
    (net (code "81") (name "Net-(IC11-O5)") (class "Default")
      (node (ref "IC11") (pin "14") (pinfunction "O5_14") (pintype "open_collector"))
      (node (ref "R26") (pin "1") (pinfunction "1_1") (pintype "passive"))
    )
    (net (code "82") (name "Net-(IC11-O6)") (class "Default")
      (node (ref "IC11") (pin "13") (pinfunction "O6_13") (pintype "open_collector"))
      (node (ref "R27") (pin "1") (pinfunction "1_1") (pintype "passive"))
    )
    (net (code "83") (name "Net-(IC11-O7)") (class "Default")
      (node (ref "IC11") (pin "12") (pinfunction "O7_12") (pintype "open_collector"))
      (node (ref "R28") (pin "1") (pinfunction "1_1") (pintype "passive"))
    )
    (net (code "84") (name "Net-(IC11-O8)") (class "Default")
      (node (ref "IC11") (pin "11") (pinfunction "O8_11") (pintype "open_collector"))
      (node (ref "R29") (pin "1") (pinfunction "1_1") (pintype "passive"))
    )
    (net (code "85") (name "Net-(IC12-O1)") (class "Default")
      (node (ref "IC12") (pin "18") (pinfunction "O1_18") (pintype "open_collector"))
      (node (ref "R30") (pin "1") (pinfunction "1_1") (pintype "passive"))
    )
    (net (code "86") (name "Net-(IC12-O2)") (class "Default")
      (node (ref "IC12") (pin "17") (pinfunction "O2_17") (pintype "open_collector"))
      (node (ref "R31") (pin "1") (pinfunction "1_1") (pintype "passive"))
    )
    (net (code "87") (name "Net-(IC12-O3)") (class "Default")
      (node (ref "IC12") (pin "16") (pinfunction "O3_16") (pintype "open_collector"))
      (node (ref "R32") (pin "1") (pinfunction "1_1") (pintype "passive"))
    )
    (net (code "88") (name "Net-(IC12-O4)") (class "Default")
      (node (ref "IC12") (pin "15") (pinfunction "O4_15") (pintype "open_collector"))
      (node (ref "R33") (pin "1") (pinfunction "1_1") (pintype "passive"))
    )
    (net (code "89") (name "Net-(IC12-O5)") (class "Default")
      (node (ref "IC12") (pin "14") (pinfunction "O5_14") (pintype "open_collector"))
      (node (ref "R34") (pin "1") (pinfunction "1_1") (pintype "passive"))
    )
    (net (code "90") (name "Net-(IC12-O6)") (class "Default")
      (node (ref "IC12") (pin "13") (pinfunction "O6_13") (pintype "open_collector"))
      (node (ref "R35") (pin "1") (pinfunction "1_1") (pintype "passive"))
    )
    (net (code "91") (name "Net-(IC12-O7)") (class "Default")
      (node (ref "IC12") (pin "12") (pinfunction "O7_12") (pintype "open_collector"))
      (node (ref "R36") (pin "1") (pinfunction "1_1") (pintype "passive"))
    )
    (net (code "92") (name "Net-(IC12-O8)") (class "Default")
      (node (ref "IC12") (pin "11") (pinfunction "O8_11") (pintype "open_collector"))
      (node (ref "R37") (pin "1") (pinfunction "1_1") (pintype "passive"))
    )
    (net (code "93") (name "Net-(IC13-+V_IN)") (class "Default")
      (node (ref "C2") (pin "+") (pinfunction "+_+") (pintype "passive"))
      (node (ref "IC13") (pin "P$1") (pinfunction "+V_IN_P$1") (pintype "passive"))
    )
    (net (code "94") (name "Net-(R1-Pad2)") (class "Default")
      (node (ref "R1") (pin "2") (pinfunction "2_2") (pintype "passive"))
      (node (ref "X5") (pin "1") (pinfunction "1_1") (pintype "passive"))
    )
    (net (code "95") (name "Net-(R8-Pad2)") (class "Default")
      (node (ref "R8") (pin "2") (pinfunction "2_2") (pintype "passive"))
      (node (ref "X6") (pin "1") (pinfunction "1_1") (pintype "passive"))
    )
    (net (code "96") (name "Net-(R15-Pad2)") (class "Default")
      (node (ref "R15") (pin "2") (pinfunction "2_2") (pintype "passive"))
      (node (ref "X7") (pin "1") (pinfunction "1_1") (pintype "passive"))
    )
    (net (code "97") (name "Net-(R22-Pad2)") (class "Default")
      (node (ref "R22") (pin "2") (pinfunction "2_2") (pintype "passive"))
      (node (ref "X3") (pin "1") (pinfunction "1_1") (pintype "passive"))
    )
    (net (code "98") (name "Net-(R30-Pad2)") (class "Default")
      (node (ref "R30") (pin "2") (pinfunction "2_2") (pintype "passive"))
      (node (ref "X1") (pin "1") (pinfunction "1_1") (pintype "passive"))
    )
    (net (code "99") (name "Net-(X1B-1)") (class "Default")
      (node (ref "R31") (pin "2") (pinfunction "2_2") (pintype "passive"))
      (node (ref "X1") (pin "2") (pinfunction "1_2") (pintype "passive"))
    )
    (net (code "100") (name "Net-(X1C-1)") (class "Default")
      (node (ref "R32") (pin "2") (pinfunction "2_2") (pintype "passive"))
      (node (ref "X1") (pin "3") (pinfunction "1_3") (pintype "passive"))
    )
    (net (code "101") (name "Net-(X1D-1)") (class "Default")
      (node (ref "R33") (pin "2") (pinfunction "2_2") (pintype "passive"))
      (node (ref "X1") (pin "4") (pinfunction "1_4") (pintype "passive"))
    )
    (net (code "102") (name "Net-(X1E-1)") (class "Default")
      (node (ref "R34") (pin "2") (pinfunction "2_2") (pintype "passive"))
      (node (ref "X1") (pin "5") (pinfunction "1_5") (pintype "passive"))
    )
    (net (code "103") (name "Net-(X1F-1)") (class "Default")
      (node (ref "R35") (pin "2") (pinfunction "2_2") (pintype "passive"))
      (node (ref "X1") (pin "6") (pinfunction "1_6") (pintype "passive"))
    )
    (net (code "104") (name "Net-(X1G-1)") (class "Default")
      (node (ref "R36") (pin "2") (pinfunction "2_2") (pintype "passive"))
      (node (ref "X1") (pin "7") (pinfunction "1_7") (pintype "passive"))
    )
    (net (code "105") (name "Net-(X1H-1)") (class "Default")
      (node (ref "R37") (pin "2") (pinfunction "2_2") (pintype "passive"))
      (node (ref "X1") (pin "8") (pinfunction "1_8") (pintype "passive"))
    )
    (net (code "106") (name "Net-(X3B-1)") (class "Default")
      (node (ref "R23") (pin "2") (pinfunction "2_2") (pintype "passive"))
      (node (ref "X3") (pin "2") (pinfunction "1_2") (pintype "passive"))
    )
    (net (code "107") (name "Net-(X3C-1)") (class "Default")
      (node (ref "R24") (pin "2") (pinfunction "2_2") (pintype "passive"))
      (node (ref "X3") (pin "3") (pinfunction "1_3") (pintype "passive"))
    )
    (net (code "108") (name "Net-(X3D-1)") (class "Default")
      (node (ref "R25") (pin "2") (pinfunction "2_2") (pintype "passive"))
      (node (ref "X3") (pin "4") (pinfunction "1_4") (pintype "passive"))
    )
    (net (code "109") (name "Net-(X3E-1)") (class "Default")
      (node (ref "R26") (pin "2") (pinfunction "2_2") (pintype "passive"))
      (node (ref "X3") (pin "5") (pinfunction "1_5") (pintype "passive"))
    )
    (net (code "110") (name "Net-(X3F-1)") (class "Default")
      (node (ref "R27") (pin "2") (pinfunction "2_2") (pintype "passive"))
      (node (ref "X3") (pin "6") (pinfunction "1_6") (pintype "passive"))
    )
    (net (code "111") (name "Net-(X3G-1)") (class "Default")
      (node (ref "R28") (pin "2") (pinfunction "2_2") (pintype "passive"))
      (node (ref "X3") (pin "7") (pinfunction "1_7") (pintype "passive"))
    )
    (net (code "112") (name "Net-(X3H-1)") (class "Default")
      (node (ref "R29") (pin "2") (pinfunction "2_2") (pintype "passive"))
      (node (ref "X3") (pin "8") (pinfunction "1_8") (pintype "passive"))
    )
    (net (code "113") (name "Net-(X5B-1)") (class "Default")
      (node (ref "R2") (pin "2") (pinfunction "2_2") (pintype "passive"))
      (node (ref "X5") (pin "2") (pinfunction "1_2") (pintype "passive"))
    )
    (net (code "114") (name "Net-(X5C-1)") (class "Default")
      (node (ref "R3") (pin "2") (pinfunction "2_2") (pintype "passive"))
      (node (ref "X5") (pin "3") (pinfunction "1_3") (pintype "passive"))
    )
    (net (code "115") (name "Net-(X5D-1)") (class "Default")
      (node (ref "R4") (pin "2") (pinfunction "2_2") (pintype "passive"))
      (node (ref "X5") (pin "4") (pinfunction "1_4") (pintype "passive"))
    )
    (net (code "116") (name "Net-(X5E-1)") (class "Default")
      (node (ref "R5") (pin "2") (pinfunction "2_2") (pintype "passive"))
      (node (ref "X5") (pin "5") (pinfunction "1_5") (pintype "passive"))
    )
    (net (code "117") (name "Net-(X5F-1)") (class "Default")
      (node (ref "R6") (pin "2") (pinfunction "2_2") (pintype "passive"))
      (node (ref "X5") (pin "6") (pinfunction "1_6") (pintype "passive"))
    )
    (net (code "118") (name "Net-(X5G-1)") (class "Default")
      (node (ref "R7") (pin "2") (pinfunction "2_2") (pintype "passive"))
      (node (ref "X5") (pin "7") (pinfunction "1_7") (pintype "passive"))
    )
    (net (code "119") (name "Net-(X6B-1)") (class "Default")
      (node (ref "R9") (pin "2") (pinfunction "2_2") (pintype "passive"))
      (node (ref "X6") (pin "2") (pinfunction "1_2") (pintype "passive"))
    )
    (net (code "120") (name "Net-(X6C-1)") (class "Default")
      (node (ref "R10") (pin "2") (pinfunction "2_2") (pintype "passive"))
      (node (ref "X6") (pin "3") (pinfunction "1_3") (pintype "passive"))
    )
    (net (code "121") (name "Net-(X6D-1)") (class "Default")
      (node (ref "R11") (pin "2") (pinfunction "2_2") (pintype "passive"))
      (node (ref "X6") (pin "4") (pinfunction "1_4") (pintype "passive"))
    )
    (net (code "122") (name "Net-(X6E-1)") (class "Default")
      (node (ref "R12") (pin "2") (pinfunction "2_2") (pintype "passive"))
      (node (ref "X6") (pin "5") (pinfunction "1_5") (pintype "passive"))
    )
    (net (code "123") (name "Net-(X6F-1)") (class "Default")
      (node (ref "R13") (pin "2") (pinfunction "2_2") (pintype "passive"))
      (node (ref "X6") (pin "6") (pinfunction "1_6") (pintype "passive"))
    )
    (net (code "124") (name "Net-(X6G-1)") (class "Default")
      (node (ref "R14") (pin "2") (pinfunction "2_2") (pintype "passive"))
      (node (ref "X6") (pin "7") (pinfunction "1_7") (pintype "passive"))
    )
    (net (code "125") (name "Net-(X7B-1)") (class "Default")
      (node (ref "R16") (pin "2") (pinfunction "2_2") (pintype "passive"))
      (node (ref "X7") (pin "2") (pinfunction "1_2") (pintype "passive"))
    )
    (net (code "126") (name "Net-(X7C-1)") (class "Default")
      (node (ref "R17") (pin "2") (pinfunction "2_2") (pintype "passive"))
      (node (ref "X7") (pin "3") (pinfunction "1_3") (pintype "passive"))
    )
    (net (code "127") (name "Net-(X7D-1)") (class "Default")
      (node (ref "R18") (pin "2") (pinfunction "2_2") (pintype "passive"))
      (node (ref "X7") (pin "4") (pinfunction "1_4") (pintype "passive"))
    )
    (net (code "128") (name "Net-(X7E-1)") (class "Default")
      (node (ref "R19") (pin "2") (pinfunction "2_2") (pintype "passive"))
      (node (ref "X7") (pin "5") (pinfunction "1_5") (pintype "passive"))
    )
    (net (code "129") (name "Net-(X7F-1)") (class "Default")
      (node (ref "R20") (pin "2") (pinfunction "2_2") (pintype "passive"))
      (node (ref "X7") (pin "6") (pinfunction "1_6") (pintype "passive"))
    )
    (net (code "130") (name "Net-(X7G-1)") (class "Default")
      (node (ref "R21") (pin "2") (pinfunction "2_2") (pintype "passive"))
      (node (ref "X7") (pin "7") (pinfunction "1_7") (pintype "passive"))
    )
    (net (code "131") (name "unconnected-(IC2-CD+-Pad9)") (class "Default")
      (node (ref "IC2") (pin "9") (pinfunction "CD+_9") (pintype "passive"))
    )
    (net (code "132") (name "unconnected-(IC4-CD+-Pad9)") (class "Default")
      (node (ref "IC4") (pin "9") (pinfunction "CD+_9") (pintype "passive"))
    )
    (net (code "133") (name "unconnected-(IC6-CD+-Pad9)") (class "Default")
      (node (ref "IC6") (pin "9") (pinfunction "CD+_9") (pintype "passive"))
    )
    (net (code "134") (name "unconnected-(IC10-QH*-Pad9)") (class "Default")
      (node (ref "IC10") (pin "9") (pinfunction "QH*_9") (pintype "tri_state"))
    )
    (net (code "135") (name "unconnected-(IC11-CD+-Pad10)") (class "Default")
      (node (ref "IC11") (pin "10") (pinfunction "CD+_10") (pintype "passive"))
    )
    (net (code "136") (name "unconnected-(IC12-CD+-Pad10)") (class "Default")
      (node (ref "IC12") (pin "10") (pinfunction "CD+_10") (pintype "passive"))
    )
    (net (code "137") (name "unconnected-(IC13-+V_OUT-PadP$2)") (class "Default")
      (node (ref "IC13") (pin "P$2") (pinfunction "+V_OUT_P$2") (pintype "output"))
    )
    (net (code "138") (name "unconnected-(IC13-FB-PadP$4)") (class "Default")
      (node (ref "IC13") (pin "P$4") (pinfunction "FB_P$4") (pintype "passive"))
    )
    (net (code "139") (name "unconnected-(U$1-A-Pad7)") (class "Default")
      (node (ref "U$1") (pin "7") (pinfunction "A_7") (pintype "passive"))
    )
    (net (code "140") (name "unconnected-(U$1-B-Pad6)") (class "Default")
      (node (ref "U$1") (pin "6") (pinfunction "B_6") (pintype "passive"))
    )
    (net (code "141") (name "unconnected-(U$1-C-Pad4)") (class "Default")
      (node (ref "U$1") (pin "4") (pinfunction "C_4") (pintype "passive"))
    )
    (net (code "142") (name "unconnected-(U$1-D-Pad2)") (class "Default")
      (node (ref "U$1") (pin "2") (pinfunction "D_2") (pintype "passive"))
    )
    (net (code "143") (name "unconnected-(U$1-DP-Pad5)") (class "Default")
      (node (ref "U$1") (pin "5") (pinfunction "DP_5") (pintype "passive"))
    )
    (net (code "144") (name "unconnected-(U$1-E-Pad1)") (class "Default")
      (node (ref "U$1") (pin "1") (pinfunction "E_1") (pintype "passive"))
    )
    (net (code "145") (name "unconnected-(U$1-F-Pad9)") (class "Default")
      (node (ref "U$1") (pin "9") (pinfunction "F_9") (pintype "passive"))
    )
    (net (code "146") (name "unconnected-(U$1-G-Pad10)") (class "Default")
      (node (ref "U$1") (pin "10") (pinfunction "G_10") (pintype "passive"))
    )
    (net (code "147") (name "unconnected-(U$1-G1-Pad3)") (class "Default")
      (node (ref "U$1") (pin "3") (pinfunction "G1_3") (pintype "passive"))
    )
    (net (code "148") (name "unconnected-(U$1-G2-Pad8)") (class "Default")
      (node (ref "U$1") (pin "8") (pinfunction "G2_8") (pintype "passive"))
    )
    (net (code "149") (name "unconnected-(U$2-A-Pad7)") (class "Default")
      (node (ref "U$2") (pin "7") (pinfunction "A_7") (pintype "passive"))
    )
    (net (code "150") (name "unconnected-(U$2-B-Pad6)") (class "Default")
      (node (ref "U$2") (pin "6") (pinfunction "B_6") (pintype "passive"))
    )
    (net (code "151") (name "unconnected-(U$2-C-Pad4)") (class "Default")
      (node (ref "U$2") (pin "4") (pinfunction "C_4") (pintype "passive"))
    )
    (net (code "152") (name "unconnected-(U$2-D-Pad2)") (class "Default")
      (node (ref "U$2") (pin "2") (pinfunction "D_2") (pintype "passive"))
    )
    (net (code "153") (name "unconnected-(U$2-DP-Pad5)") (class "Default")
      (node (ref "U$2") (pin "5") (pinfunction "DP_5") (pintype "passive"))
    )
    (net (code "154") (name "unconnected-(U$2-E-Pad1)") (class "Default")
      (node (ref "U$2") (pin "1") (pinfunction "E_1") (pintype "passive"))
    )
    (net (code "155") (name "unconnected-(U$2-F-Pad9)") (class "Default")
      (node (ref "U$2") (pin "9") (pinfunction "F_9") (pintype "passive"))
    )
    (net (code "156") (name "unconnected-(U$2-G-Pad10)") (class "Default")
      (node (ref "U$2") (pin "10") (pinfunction "G_10") (pintype "passive"))
    )
    (net (code "157") (name "unconnected-(U$2-G1-Pad3)") (class "Default")
      (node (ref "U$2") (pin "3") (pinfunction "G1_3") (pintype "passive"))
    )
    (net (code "158") (name "unconnected-(U$2-G2-Pad8)") (class "Default")
      (node (ref "U$2") (pin "8") (pinfunction "G2_8") (pintype "passive"))
    )
    (net (code "159") (name "unconnected-(U$3-A-Pad7)") (class "Default")
      (node (ref "U$3") (pin "7") (pinfunction "A_7") (pintype "passive"))
    )
    (net (code "160") (name "unconnected-(U$3-B-Pad6)") (class "Default")
      (node (ref "U$3") (pin "6") (pinfunction "B_6") (pintype "passive"))
    )
    (net (code "161") (name "unconnected-(U$3-C-Pad4)") (class "Default")
      (node (ref "U$3") (pin "4") (pinfunction "C_4") (pintype "passive"))
    )
    (net (code "162") (name "unconnected-(U$3-D-Pad2)") (class "Default")
      (node (ref "U$3") (pin "2") (pinfunction "D_2") (pintype "passive"))
    )
    (net (code "163") (name "unconnected-(U$3-DP-Pad5)") (class "Default")
      (node (ref "U$3") (pin "5") (pinfunction "DP_5") (pintype "passive"))
    )
    (net (code "164") (name "unconnected-(U$3-E-Pad1)") (class "Default")
      (node (ref "U$3") (pin "1") (pinfunction "E_1") (pintype "passive"))
    )
    (net (code "165") (name "unconnected-(U$3-F-Pad9)") (class "Default")
      (node (ref "U$3") (pin "9") (pinfunction "F_9") (pintype "passive"))
    )
    (net (code "166") (name "unconnected-(U$3-G-Pad10)") (class "Default")
      (node (ref "U$3") (pin "10") (pinfunction "G_10") (pintype "passive"))
    )
    (net (code "167") (name "unconnected-(U$3-G1-Pad3)") (class "Default")
      (node (ref "U$3") (pin "3") (pinfunction "G1_3") (pintype "passive"))
    )
    (net (code "168") (name "unconnected-(U$3-G2-Pad8)") (class "Default")
      (node (ref "U$3") (pin "8") (pinfunction "G2_8") (pintype "passive"))
    )
    (net (code "169") (name "unconnected-(U1-A4{slash}SDA-PadA4)") (class "Default")
      (node (ref "U1") (pin "A4") (pinfunction "A4/SDA_A4") (pintype "passive"))
    )
    (net (code "170") (name "unconnected-(U1-A5{slash}SCL-PadA5)") (class "Default")
      (node (ref "U1") (pin "A5") (pinfunction "A5/SCL_A5") (pintype "passive"))
    )
    (net (code "171") (name "unconnected-(U1-Pad3V)") (class "Default")
      (node (ref "U1") (pin "3V") (pinfunction "3V_3V") (pintype "power_in"))
    )
    (net (code "172") (name "unconnected-(U1-Pad5V)") (class "Default")
      (node (ref "U1") (pin "5V") (pinfunction "5V_5V") (pintype "power_in"))
    )
    (net (code "173") (name "unconnected-(U1-PadA0)") (class "Default")
      (node (ref "U1") (pin "A0") (pinfunction "A0_A0") (pintype "passive"))
    )
    (net (code "174") (name "unconnected-(U1-PadA1)") (class "Default")
      (node (ref "U1") (pin "A1") (pinfunction "A1_A1") (pintype "passive"))
    )
    (net (code "175") (name "unconnected-(U1-PadA2)") (class "Default")
      (node (ref "U1") (pin "A2") (pinfunction "A2_A2") (pintype "passive"))
    )
    (net (code "176") (name "unconnected-(U1-PadA3)") (class "Default")
      (node (ref "U1") (pin "A3") (pinfunction "A3_A3") (pintype "passive"))
    )
    (net (code "177") (name "unconnected-(U1-PadAREF)") (class "Default")
      (node (ref "U1") (pin "AREF") (pinfunction "AREF_AREF") (pintype "passive"))
    )
    (net (code "178") (name "unconnected-(U1-PadD12)") (class "Default")
      (node (ref "U1") (pin "D12") (pinfunction "D12_D12") (pintype "passive"))
    )
    (net (code "179") (name "unconnected-(U1-PadD13)") (class "Default")
      (node (ref "U1") (pin "D13") (pinfunction "D13_D13") (pintype "passive"))
    )
    (net (code "180") (name "unconnected-(U1-PadGND1)") (class "Default")
      (node (ref "U1") (pin "GND1") (pinfunction "GND1_GND1") (pintype "power_in"))
    )
    (net (code "181") (name "unconnected-(U1-PadGND2)") (class "Default")
      (node (ref "U1") (pin "GND2") (pinfunction "GND2_GND2") (pintype "power_in"))
    )
    (net (code "182") (name "unconnected-(U1-PadIOREF)") (class "Default")
      (node (ref "U1") (pin "IOREF") (pinfunction "IOREF_IOREF") (pintype "output"))
    )
    (net (code "183") (name "unconnected-(U1-PadRESERVED)") (class "Default")
      (node (ref "U1") (pin "RESERVED") (pinfunction "RESERVED_RESERVED") (pintype "passive"))
    )
    (net (code "184") (name "unconnected-(U1-PadSCL)") (class "Default")
      (node (ref "U1") (pin "SCL") (pinfunction "SCL_SCL") (pintype "passive"))
    )
    (net (code "185") (name "unconnected-(U1-PadSDA)") (class "Default")
      (node (ref "U1") (pin "SDA") (pinfunction "SDA_SDA") (pintype "passive"))
    )
    (net (code "186") (name "unconnected-(U1-{slash}RESET-PadRESET)") (class "Default")
      (node (ref "U1") (pin "RESET") (pinfunction "/RESET_RESET") (pintype "passive"))
    )
  )
)
